# 04_-_3_inch.net
KiCad netlist of a schematic drawn in Altium Designer
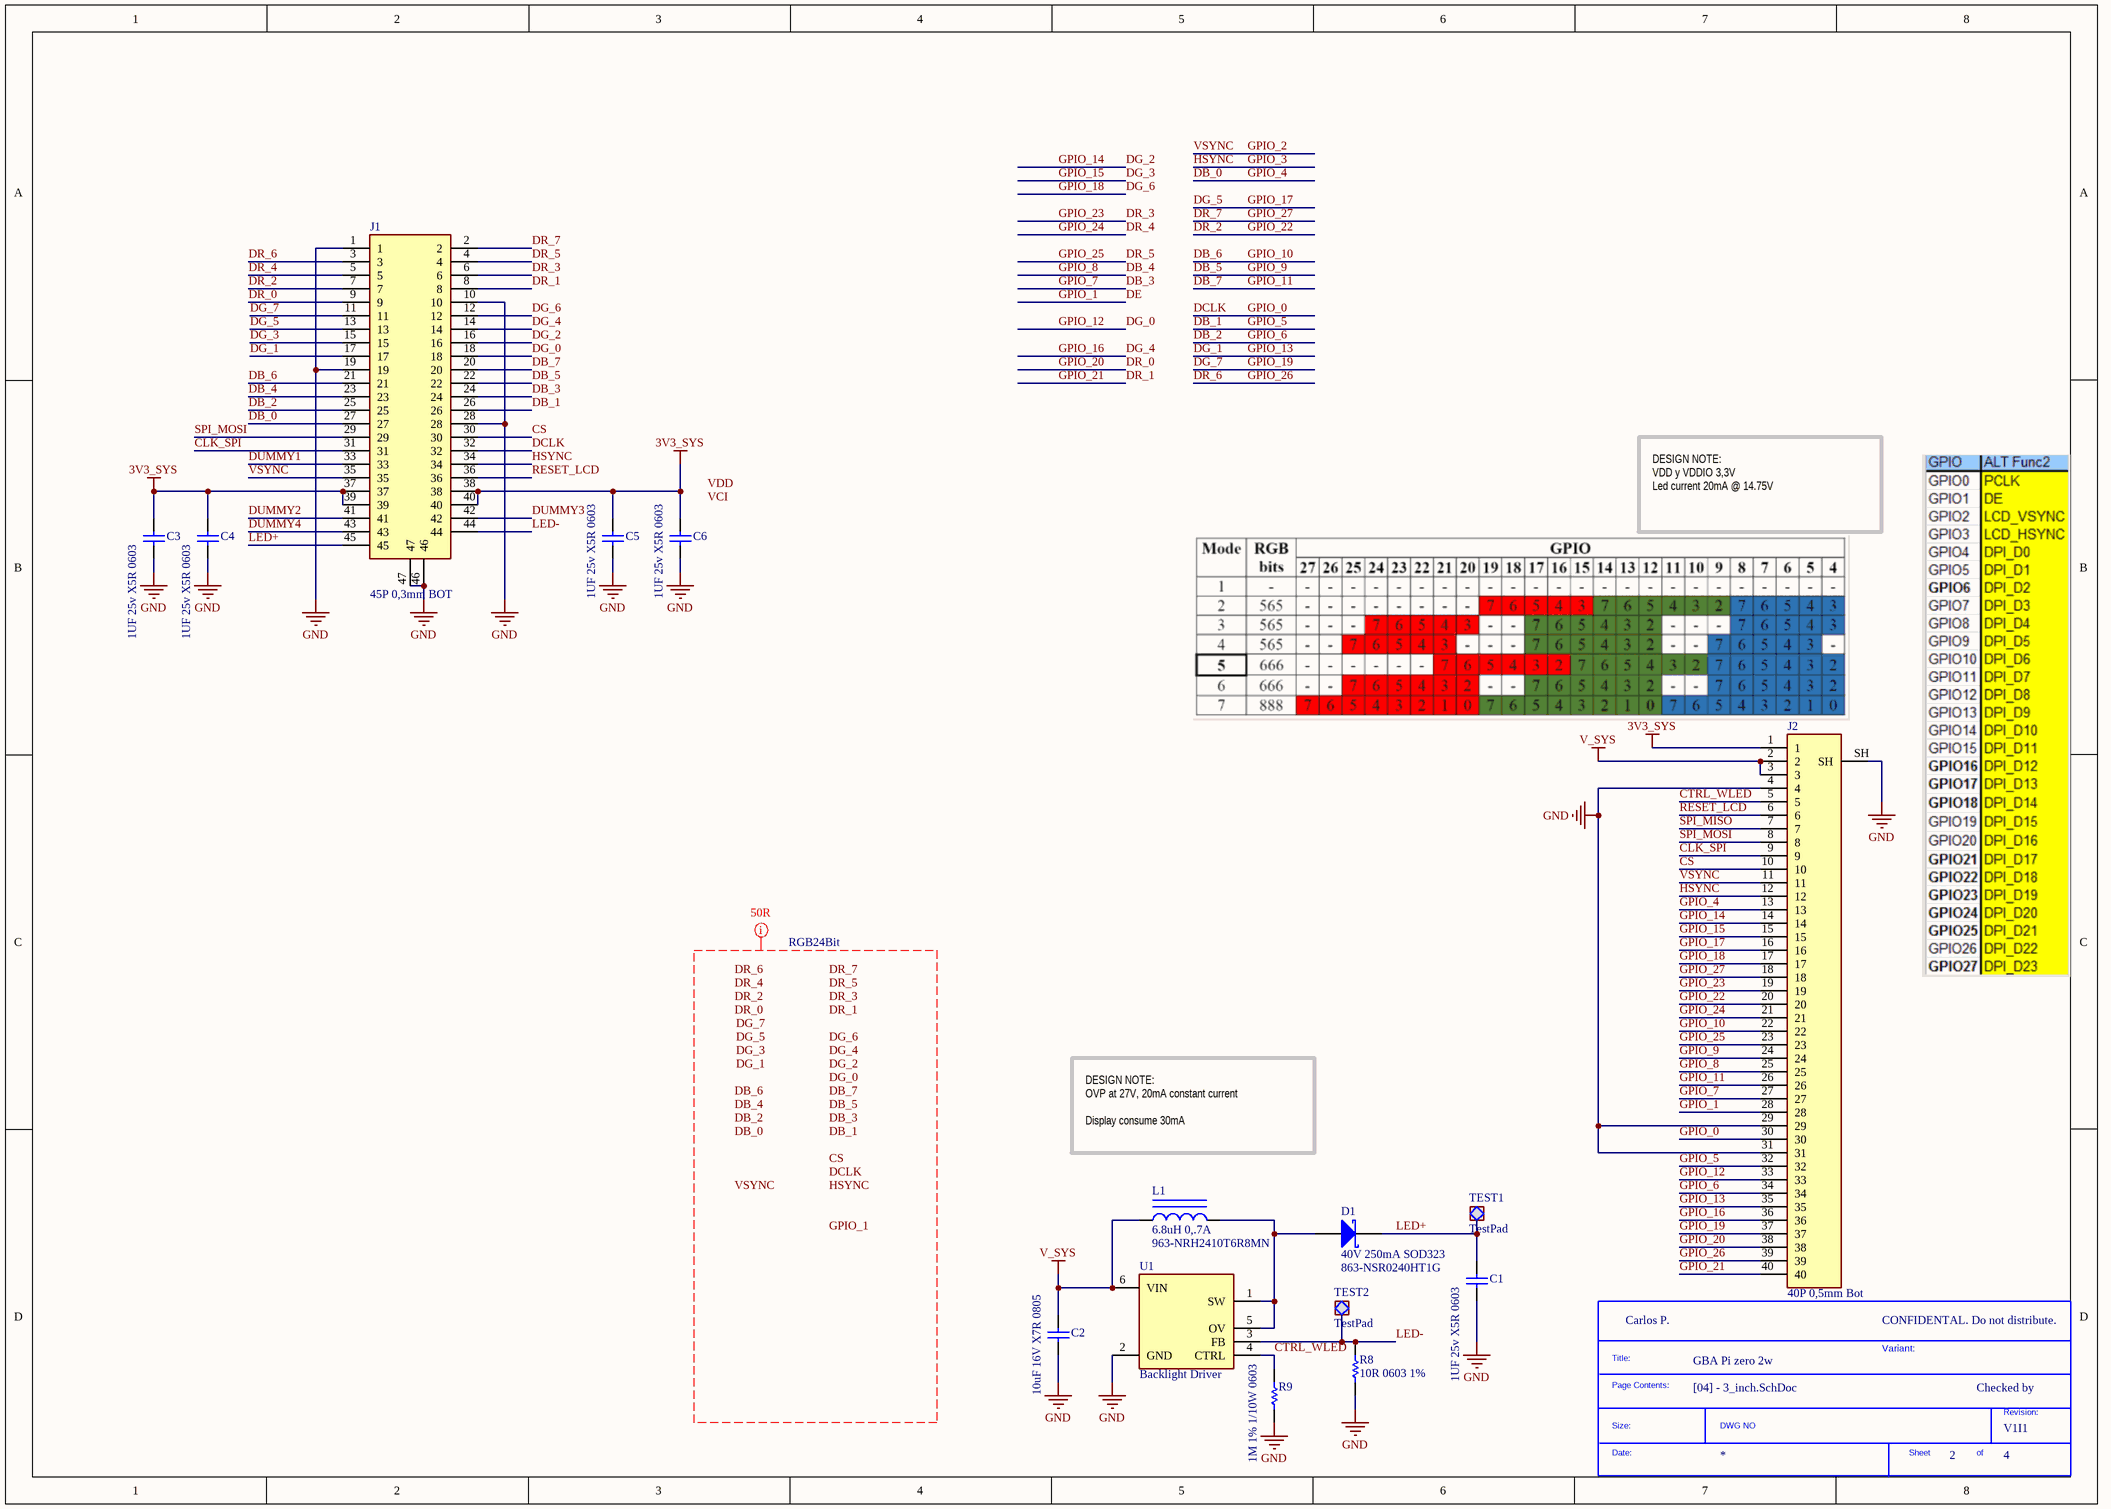
[diagram p0: [04] - 3_inch.SchDoc]

(export (version "E")
  (design (tool "Eeschema 10.0.6"))
  (components
    (comp (ref "C1")
      (value "1UF 25v X5R 0603")
      (footprint "C 0603/1608")
      (description "CAP CER 1UF 25V X5R 0603")
      (fields
        (field (name "MANUFACTURER") "Yageo")
        (field (name "MANUFACTURER PART NUMBER") "CC0603KRX5R8BB105")
      )
      (libsource (lib "CM3Board_V1I2") (part "CC0603KRX5R8BB105"))
    )
    (comp (ref "C2")
      (value "10uF 16V X7R 0805")
      (footprint "C 0805/2012")
      (description "CAP CER 10UF 16V X7R 0805")
      (fields
        (field (name "MANUFACTURER") "Samsung Electro-Mechanics")
        (field (name "MANUFACTURER PART NUMBER") "CL21B106KOQNNNE")
      )
      (libsource (lib "CM3Board_V1I2") (part "CL21B106KOQNNNE"))
    )
    (comp (ref "C3")
      (value "1UF 25v X5R 0603")
      (footprint "C 0603/1608")
      (description "CAP CER 1UF 25V X5R 0603")
      (fields
        (field (name "MANUFACTURER") "Yageo")
        (field (name "MANUFACTURER PART NUMBER") "CC0603KRX5R8BB105")
      )
      (libsource (lib "CM3Board_V1I2") (part "CC0603KRX5R8BB105"))
    )
    (comp (ref "C4")
      (value "1UF 25v X5R 0603")
      (footprint "C 0603/1608")
      (description "CAP CER 1UF 25V X5R 0603")
      (fields
        (field (name "MANUFACTURER") "Yageo")
        (field (name "MANUFACTURER PART NUMBER") "CC0603KRX5R8BB105")
      )
      (libsource (lib "CM3Board_V1I2") (part "CC0603KRX5R8BB105"))
    )
    (comp (ref "C5")
      (value "1UF 25v X5R 0603")
      (footprint "C 0603/1608")
      (description "CAP CER 1UF 25V X5R 0603")
      (fields
        (field (name "MANUFACTURER") "Yageo")
        (field (name "MANUFACTURER PART NUMBER") "CC0603KRX5R8BB105")
      )
      (libsource (lib "CM3Board_V1I2") (part "CC0603KRX5R8BB105"))
    )
    (comp (ref "C6")
      (value "1UF 25v X5R 0603")
      (footprint "C 0603/1608")
      (description "CAP CER 1UF 25V X5R 0603")
      (fields
        (field (name "MANUFACTURER") "Yageo")
        (field (name "MANUFACTURER PART NUMBER") "CC0603KRX5R8BB105")
      )
      (libsource (lib "CM3Board_V1I2") (part "CC0603KRX5R8BB105"))
    )
    (comp (ref "D1")
      (value "40V 250mA SOD323")
      (footprint "SOD-323")
      (description "DIODE SCHOTTKY 40V 250MA SOD323")
      (fields
        (field (name "MANUFACTURER") "ON Semiconductor")
        (field (name "MANUFACTURER PART NUMBER") "NSR0240HT1G")
        (field (name "SUPPLIER PART NUMBER 1") "863-NSR0240HT1G")
      )
      (libsource (lib "DPI_LVDS") (part "NSR0240HT1G"))
    )
    (comp (ref "J1")
      (value "45P 0,3mm BOT")
      (footprint "FH26W45S03SHW60")
      (description "FFC FPC Connectors Horizontal Mounting Angle Light Brown 0.3 mm - Pitch 45 Positions")
      (fields
        (field (name "MANUFACTURER") "Hirose")
        (field (name "MANUFACTURER PART NUMBER") "FH26W-45S-0.3SHW(60)")
      )
      (libsource (lib "GBA") (part "FH26W-45S-0.3SHW(60)"))
    )
    (comp (ref "J2")
      (value "40P 0,5mm Bot")
      (footprint "417345920")
      (description "CONN FPC BOTTOM 40POS 0.50MM R/A")
      (fields
        (field (name "MANUFACTURER") "TE Connectivity")
        (field (name "MANUFACTURER PART NUMBER") "4-1734592-0")
      )
      (libsource (lib "GBA") (part "4-1734592-0"))
    )
    (comp (ref "L1")
      (value "6.8uH 0,.7A")
      (footprint "NRH2410T6R8MN")
      (description "Inductor Power Shielded Wirewound 6.8uH 20% 100KHz Ferrite 0.57A 0.492Ohm DCR T/R")
      (fields
        (field (name "MANUFACTURER") "Taiyo Yuden")
        (field (name "MANUFACTURER PART NUMBER") "NRH2410T6R8MN")
        (field (name "SUPPLIER PART NUMBER 1") "963-NRH2410T6R8MN")
      )
      (libsource (lib "GBA") (part "NRH2410T6R8MN"))
    )
    (comp (ref "R8")
      (value "10R 0603 1%")
      (footprint "R 0603/1608")
      (description "High Precision-High Stability Chip Resistor Thin Film 0603 10Ohm 1% Paper T/R")
      (fields
        (field (name "MANUFACTURER") "Yageo")
        (field (name "MANUFACTURER PART NUMBER") "RT0603FRE0710RL")
      )
      (libsource (lib "GBA") (part "RT0603FRE0710RL"))
    )
    (comp (ref "R9")
      (value "1M 1% 1/10W 0603")
      (footprint "R 0603/1608")
      (description "RES SMD 1M OHM 1% 1/10W 0603")
      (fields (field (name "TOLERANCE") "1%"))
      (libsource (lib "CM3Board_V1I2") (part "RC0603FR-071ML"))
    )
    (comp (ref "TEST1")
      (value "TestPad")
      (footprint "TestPad")
      (description "Probe Pad, SMT, ROUND, 2.0MM")
      (libsource (lib "CM3Board") (part "PP_SMT_ROUND_2MM"))
    )
    (comp (ref "TEST2")
      (value "TestPad")
      (footprint "TestPad")
      (description "Probe Pad, SMT, ROUND, 2.0MM")
      (libsource (lib "CM3Board") (part "PP_SMT_ROUND_2MM"))
    )
    (comp (ref "U1")
      (value "Backlight Driver")
      (footprint "SOT95P280X145-6N")
      (description "AP3032 Series 9 V 1.3 MHz Surface Mount White LED Step-Up Converter - SOT-23-6")
      (fields (field (name "MANUFACTURER") "Diodes") (field (name "MANUFACTURER PART NUMBER") "AP3032KTR-G1"))
      (libsource (lib "GBA") (part "AP3032KTR-G1"))
    )
  )
  (nets
    (net (code "1") (name "/CLK_SPI") (class "Default")
      (node (ref "J1") (pin "31") (pinfunction "31_31") (pintype "passive"))
      (node (ref "J2") (pin "9") (pinfunction "9_9") (pintype "passive"))
    )
    (net (code "2") (name "/CS") (class "Default")
      (node (ref "J1") (pin "30") (pinfunction "30_30") (pintype "passive"))
      (node (ref "J2") (pin "10") (pinfunction "10_10") (pintype "passive"))
    )
    (net (code "3") (name "/CTRL_WLED") (class "Default")
      (node (ref "J2") (pin "5") (pinfunction "5_5") (pintype "passive"))
      (node (ref "R9") (pin "2") (pinfunction "2_2") (pintype "passive"))
      (node (ref "U1") (pin "4") (pinfunction "CTRL_4") (pintype "passive"))
    )
    (net (code "4") (name "/DB_0") (class "Default")
      (node (ref "J1") (pin "27") (pinfunction "27_27") (pintype "passive"))
      (node (ref "J2") (pin "13") (pinfunction "13_13") (pintype "passive"))
    )
    (net (code "5") (name "/DB_1") (class "Default")
      (node (ref "J1") (pin "26") (pinfunction "26_26") (pintype "passive"))
      (node (ref "J2") (pin "32") (pinfunction "32_32") (pintype "passive"))
    )
    (net (code "6") (name "/DB_2") (class "Default")
      (node (ref "J1") (pin "25") (pinfunction "25_25") (pintype "passive"))
      (node (ref "J2") (pin "34") (pinfunction "34_34") (pintype "passive"))
    )
    (net (code "7") (name "/DB_3") (class "Default")
      (node (ref "J1") (pin "24") (pinfunction "24_24") (pintype "passive"))
      (node (ref "J2") (pin "27") (pinfunction "27_27") (pintype "passive"))
    )
    (net (code "8") (name "/DB_4") (class "Default")
      (node (ref "J1") (pin "23") (pinfunction "23_23") (pintype "passive"))
      (node (ref "J2") (pin "25") (pinfunction "25_25") (pintype "passive"))
    )
    (net (code "9") (name "/DB_5") (class "Default")
      (node (ref "J1") (pin "22") (pinfunction "22_22") (pintype "passive"))
      (node (ref "J2") (pin "24") (pinfunction "24_24") (pintype "passive"))
    )
    (net (code "10") (name "/DB_6") (class "Default")
      (node (ref "J1") (pin "21") (pinfunction "21_21") (pintype "passive"))
      (node (ref "J2") (pin "22") (pinfunction "22_22") (pintype "passive"))
    )
    (net (code "11") (name "/DB_7") (class "Default")
      (node (ref "J1") (pin "20") (pinfunction "20_20") (pintype "passive"))
      (node (ref "J2") (pin "26") (pinfunction "26_26") (pintype "passive"))
    )
    (net (code "12") (name "/DCLK") (class "Default")
      (node (ref "J1") (pin "32") (pinfunction "32_32") (pintype "passive"))
      (node (ref "J2") (pin "30") (pinfunction "30_30") (pintype "passive"))
    )
    (net (code "13") (name "/DE") (class "Default")
      (node (ref "J2") (pin "28") (pinfunction "28_28") (pintype "passive"))
    )
    (net (code "14") (name "/DG_0") (class "Default")
      (node (ref "J1") (pin "18") (pinfunction "18_18") (pintype "passive"))
      (node (ref "J2") (pin "33") (pinfunction "33_33") (pintype "passive"))
    )
    (net (code "15") (name "/DG_1") (class "Default")
      (node (ref "J1") (pin "17") (pinfunction "17_17") (pintype "passive"))
      (node (ref "J2") (pin "35") (pinfunction "35_35") (pintype "passive"))
    )
    (net (code "16") (name "/DG_2") (class "Default")
      (node (ref "J1") (pin "16") (pinfunction "16_16") (pintype "passive"))
      (node (ref "J2") (pin "14") (pinfunction "14_14") (pintype "passive"))
    )
    (net (code "17") (name "/DG_3") (class "Default")
      (node (ref "J1") (pin "15") (pinfunction "15_15") (pintype "passive"))
      (node (ref "J2") (pin "15") (pinfunction "15_15") (pintype "passive"))
    )
    (net (code "18") (name "/DG_4") (class "Default")
      (node (ref "J1") (pin "14") (pinfunction "14_14") (pintype "passive"))
      (node (ref "J2") (pin "36") (pinfunction "36_36") (pintype "passive"))
    )
    (net (code "19") (name "/DG_5") (class "Default")
      (node (ref "J1") (pin "13") (pinfunction "13_13") (pintype "passive"))
      (node (ref "J2") (pin "16") (pinfunction "16_16") (pintype "passive"))
    )
    (net (code "20") (name "/DG_6") (class "Default")
      (node (ref "J1") (pin "12") (pinfunction "12_12") (pintype "passive"))
      (node (ref "J2") (pin "17") (pinfunction "17_17") (pintype "passive"))
    )
    (net (code "21") (name "/DG_7") (class "Default")
      (node (ref "J1") (pin "11") (pinfunction "11_11") (pintype "passive"))
      (node (ref "J2") (pin "37") (pinfunction "37_37") (pintype "passive"))
    )
    (net (code "22") (name "/DR_0") (class "Default")
      (node (ref "J1") (pin "9") (pinfunction "9_9") (pintype "passive"))
      (node (ref "J2") (pin "38") (pinfunction "38_38") (pintype "passive"))
    )
    (net (code "23") (name "/DR_1") (class "Default")
      (node (ref "J1") (pin "8") (pinfunction "8_8") (pintype "passive"))
      (node (ref "J2") (pin "40") (pinfunction "40_40") (pintype "passive"))
    )
    (net (code "24") (name "/DR_2") (class "Default")
      (node (ref "J1") (pin "7") (pinfunction "7_7") (pintype "passive"))
      (node (ref "J2") (pin "20") (pinfunction "20_20") (pintype "passive"))
    )
    (net (code "25") (name "/DR_3") (class "Default")
      (node (ref "J1") (pin "6") (pinfunction "6_6") (pintype "passive"))
      (node (ref "J2") (pin "19") (pinfunction "19_19") (pintype "passive"))
    )
    (net (code "26") (name "/DR_4") (class "Default")
      (node (ref "J1") (pin "5") (pinfunction "5_5") (pintype "passive"))
      (node (ref "J2") (pin "21") (pinfunction "21_21") (pintype "passive"))
    )
    (net (code "27") (name "/DR_5") (class "Default")
      (node (ref "J1") (pin "4") (pinfunction "4_4") (pintype "passive"))
      (node (ref "J2") (pin "23") (pinfunction "23_23") (pintype "passive"))
    )
    (net (code "28") (name "/DR_6") (class "Default")
      (node (ref "J1") (pin "3") (pinfunction "3_3") (pintype "passive"))
      (node (ref "J2") (pin "39") (pinfunction "39_39") (pintype "passive"))
    )
    (net (code "29") (name "/DR_7") (class "Default")
      (node (ref "J1") (pin "2") (pinfunction "2_2") (pintype "passive"))
      (node (ref "J2") (pin "18") (pinfunction "18_18") (pintype "passive"))
    )
    (net (code "30") (name "/DUMMY1") (class "Default")
      (node (ref "J1") (pin "33") (pinfunction "33_33") (pintype "passive"))
    )
    (net (code "31") (name "/DUMMY2") (class "Default")
      (node (ref "J1") (pin "41") (pinfunction "41_41") (pintype "passive"))
    )
    (net (code "32") (name "/DUMMY3") (class "Default")
      (node (ref "J1") (pin "42") (pinfunction "42_42") (pintype "passive"))
    )
    (net (code "33") (name "/DUMMY4") (class "Default")
      (node (ref "J1") (pin "43") (pinfunction "43_43") (pintype "passive"))
    )
    (net (code "34") (name "/GPIO_2") (class "Default")
      (node (ref "J1") (pin "35") (pinfunction "35_35") (pintype "passive"))
      (node (ref "J2") (pin "11") (pinfunction "11_11") (pintype "passive"))
    )
    (net (code "35") (name "/GPIO_3") (class "Default")
      (node (ref "J1") (pin "34") (pinfunction "34_34") (pintype "passive"))
      (node (ref "J2") (pin "12") (pinfunction "12_12") (pintype "passive"))
    )
    (net (code "36") (name "/LED+") (class "Default")
      (node (ref "C1") (pin "1") (pinfunction "1_1") (pintype "passive"))
      (node (ref "D1") (pin "1") (pinfunction "K_1") (pintype "passive"))
      (node (ref "J1") (pin "45") (pinfunction "45_45") (pintype "passive"))
      (node (ref "TEST1") (pin "1") (pinfunction "1_1") (pintype "passive"))
    )
    (net (code "37") (name "/LED-") (class "Default")
      (node (ref "J1") (pin "44") (pinfunction "44_44") (pintype "passive"))
      (node (ref "R8") (pin "2") (pinfunction "2_2") (pintype "passive"))
      (node (ref "TEST2") (pin "1") (pinfunction "1_1") (pintype "passive"))
      (node (ref "U1") (pin "3") (pinfunction "FB_3") (pintype "passive"))
    )
    (net (code "38") (name "/RESET_LCD") (class "Default")
      (node (ref "J1") (pin "36") (pinfunction "36_36") (pintype "passive"))
      (node (ref "J2") (pin "6") (pinfunction "6_6") (pintype "passive"))
    )
    (net (code "39") (name "/SPI_MISO") (class "Default")
      (node (ref "J2") (pin "7") (pinfunction "7_7") (pintype "passive"))
    )
    (net (code "40") (name "/SPI_MOSI") (class "Default")
      (node (ref "J1") (pin "29") (pinfunction "29_29") (pintype "passive"))
      (node (ref "J2") (pin "8") (pinfunction "8_8") (pintype "passive"))
    )
    (net (code "43") (name "3V3_SYS") (class "Default")
      (node (ref "C3") (pin "1") (pinfunction "1_1") (pintype "passive"))
      (node (ref "C4") (pin "1") (pinfunction "1_1") (pintype "passive"))
      (node (ref "C5") (pin "1") (pinfunction "1_1") (pintype "passive"))
      (node (ref "C6") (pin "1") (pinfunction "1_1") (pintype "passive"))
      (node (ref "J1") (pin "37") (pinfunction "37_37") (pintype "passive"))
      (node (ref "J1") (pin "38") (pinfunction "38_38") (pintype "passive"))
      (node (ref "J1") (pin "39") (pinfunction "39_39") (pintype "passive"))
      (node (ref "J1") (pin "40") (pinfunction "40_40") (pintype "passive"))
      (node (ref "J2") (pin "1") (pinfunction "1_1") (pintype "passive"))
    )
    (net (code "44") (name "GND") (class "Default")
      (node (ref "C1") (pin "2") (pinfunction "2_2") (pintype "passive"))
      (node (ref "C2") (pin "1") (pinfunction "1_1") (pintype "passive"))
      (node (ref "C3") (pin "2") (pinfunction "2_2") (pintype "passive"))
      (node (ref "C4") (pin "2") (pinfunction "2_2") (pintype "passive"))
      (node (ref "C5") (pin "2") (pinfunction "2_2") (pintype "passive"))
      (node (ref "C6") (pin "2") (pinfunction "2_2") (pintype "passive"))
      (node (ref "J1") (pin "1") (pinfunction "1_1") (pintype "passive"))
      (node (ref "J1") (pin "10") (pinfunction "10_10") (pintype "passive"))
      (node (ref "J1") (pin "19") (pinfunction "19_19") (pintype "passive"))
      (node (ref "J1") (pin "28") (pinfunction "28_28") (pintype "passive"))
      (node (ref "J1") (pin "46") (pinfunction "46_46") (pintype "passive"))
      (node (ref "J1") (pin "47") (pinfunction "47_47") (pintype "passive"))
      (node (ref "J2") (pin "29") (pinfunction "29_29") (pintype "passive"))
      (node (ref "J2") (pin "31") (pinfunction "31_31") (pintype "passive"))
      (node (ref "J2") (pin "4") (pinfunction "4_4") (pintype "passive"))
      (node (ref "J2") (pin "SH") (pinfunction "SH_SH") (pintype "passive"))
      (node (ref "R8") (pin "1") (pinfunction "1_1") (pintype "passive"))
      (node (ref "R9") (pin "1") (pinfunction "1_1") (pintype "passive"))
      (node (ref "U1") (pin "2") (pinfunction "GND_2") (pintype "passive"))
    )
    (net (code "45") (name "Net-(D1-A)") (class "Default")
      (node (ref "D1") (pin "2") (pinfunction "A_2") (pintype "passive"))
      (node (ref "L1") (pin "2") (pinfunction "2_2") (pintype "passive"))
      (node (ref "U1") (pin "1") (pinfunction "SW_1") (pintype "passive"))
      (node (ref "U1") (pin "5") (pinfunction "OV_5") (pintype "passive"))
    )
    (net (code "46") (name "V_SYS") (class "Default")
      (node (ref "C2") (pin "2") (pinfunction "2_2") (pintype "passive"))
      (node (ref "J2") (pin "2") (pinfunction "2_2") (pintype "passive"))
      (node (ref "J2") (pin "3") (pinfunction "3_3") (pintype "passive"))
      (node (ref "L1") (pin "1") (pinfunction "1_1") (pintype "passive"))
      (node (ref "U1") (pin "6") (pinfunction "VIN_6") (pintype "passive"))
    )
  )
)
